# psu_2_1.net
KiCad netlist of a schematic drawn in EAGLE
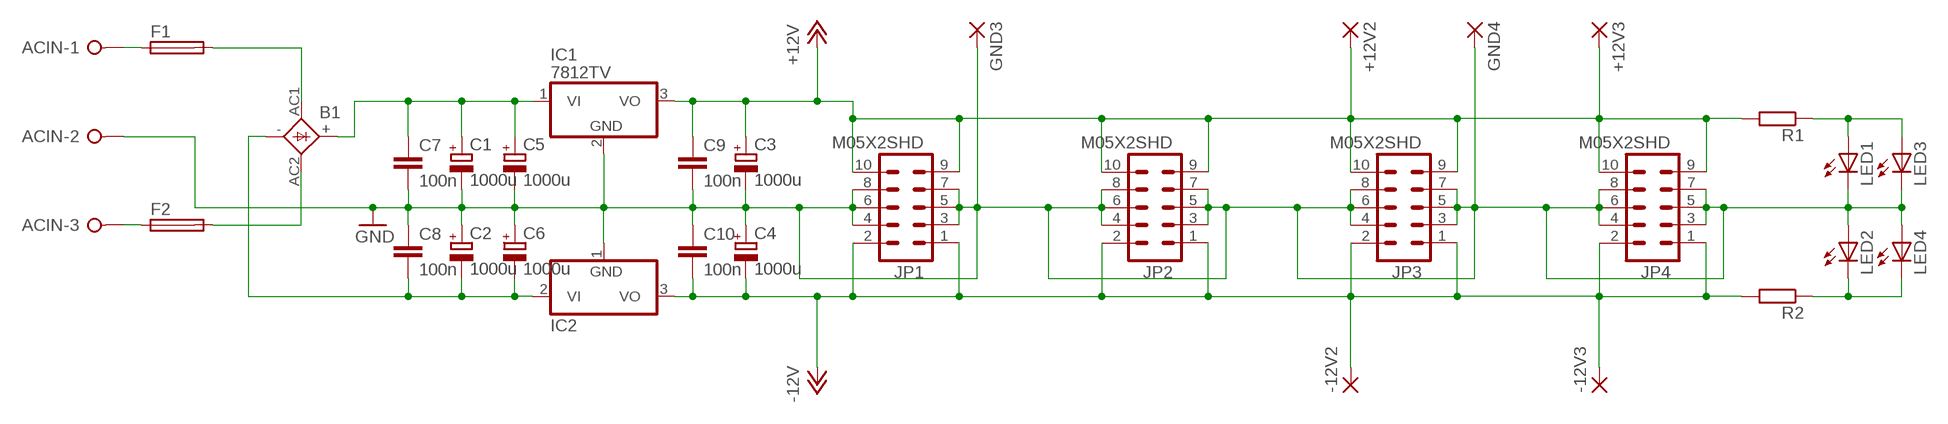
[diagram p0: schematic, sheet 1]

(export (version "E")
  (design (tool "Eeschema 10.0.6"))
  (components
    (comp (ref "+12V2")
      (value "2,54/1,0")
      (footprint "eagle-import:2,54_1,0")
      (libsource (lib "eagle-import") (part "2,54/1,0"))
    )
    (comp (ref "+12V3")
      (value "2,54/1,0")
      (footprint "eagle-import:2,54_1,0")
      (libsource (lib "eagle-import") (part "2,54/1,0"))
    )
    (comp (ref "-12V2")
      (value "2,54/1,0")
      (footprint "eagle-import:2,54_1,0")
      (libsource (lib "eagle-import") (part "2,54/1,0"))
    )
    (comp (ref "-12V3")
      (value "2,54/1,0")
      (footprint "eagle-import:2,54_1,0")
      (libsource (lib "eagle-import") (part "2,54/1,0"))
    )
    (comp (ref "ACIN")
      (value "W237-3E")
      (footprint "eagle-import:W237-3E")
      (libsource (lib "eagle-import") (part "W237-3E"))
    )
    (comp (ref "B1")
      (value "2KBP")
      (footprint "eagle-import:2KBP")
      (libsource (lib "eagle-import") (part "2KBP"))
    )
    (comp (ref "C1")
      (value "1000u")
      (footprint "eagle-import:E3,5-10")
      (libsource (lib "eagle-import") (part "CPOL-EUE3.5-10"))
    )
    (comp (ref "C2")
      (value "1000u")
      (footprint "eagle-import:E3,5-10")
      (libsource (lib "eagle-import") (part "CPOL-EUE3.5-10"))
    )
    (comp (ref "C3")
      (value "1000u")
      (footprint "eagle-import:E3,5-10")
      (libsource (lib "eagle-import") (part "CPOL-EUE3.5-10"))
    )
    (comp (ref "C4")
      (value "1000u")
      (footprint "eagle-import:E3,5-10")
      (libsource (lib "eagle-import") (part "CPOL-EUE3.5-10"))
    )
    (comp (ref "C5")
      (value "1000u")
      (footprint "eagle-import:E3,5-10")
      (libsource (lib "eagle-import") (part "CPOL-EUE3.5-10"))
    )
    (comp (ref "C6")
      (value "1000u")
      (footprint "eagle-import:E3,5-10")
      (libsource (lib "eagle-import") (part "CPOL-EUE3.5-10"))
    )
    (comp (ref "C7")
      (value "100n")
      (footprint "eagle-import:C1206K")
      (libsource (lib "eagle-import") (part "C-EUC1206K"))
    )
    (comp (ref "C8")
      (value "100n")
      (footprint "eagle-import:C1206K")
      (libsource (lib "eagle-import") (part "C-EUC1206K"))
    )
    (comp (ref "C9")
      (value "100n")
      (footprint "eagle-import:C1206K")
      (libsource (lib "eagle-import") (part "C-EUC1206K"))
    )
    (comp (ref "C10")
      (value "100n")
      (footprint "eagle-import:C1206K")
      (libsource (lib "eagle-import") (part "C-EUC1206K"))
    )
    (comp (ref "F1")
      (value "19560")
      (footprint "eagle-import:19560")
      (fields (field (name "MPN") "56000001009"))
      (libsource (lib "eagle-import") (part "19560"))
    )
    (comp (ref "F2")
      (value "19560")
      (footprint "eagle-import:19560")
      (fields (field (name "MPN") "56000001009"))
      (libsource (lib "eagle-import") (part "19560"))
    )
    (comp (ref "GND3")
      (value "2,54/1,0")
      (footprint "eagle-import:2,54_1,0")
      (libsource (lib "eagle-import") (part "2,54/1,0"))
    )
    (comp (ref "GND4")
      (value "2,54/1,0")
      (footprint "eagle-import:2,54_1,0")
      (libsource (lib "eagle-import") (part "2,54/1,0"))
    )
    (comp (ref "IC1")
      (value "7812TV")
      (footprint "eagle-import:TO220V")
      (libsource (lib "eagle-import") (part "78TV12"))
    )
    (comp (ref "IC2")
      (value "7912TV")
      (footprint "eagle-import:TO220V")
      (libsource (lib "eagle-import") (part "79TV12"))
    )
    (comp (ref "JP1")
      (value "M05X2SHD")
      (footprint "eagle-import:2X5-SHROUDED")
      (libsource (lib "eagle-import") (part "M05X2SHD"))
    )
    (comp (ref "JP2")
      (value "M05X2SHD")
      (footprint "eagle-import:2X5-SHROUDED")
      (libsource (lib "eagle-import") (part "M05X2SHD"))
    )
    (comp (ref "JP3")
      (value "M05X2SHD")
      (footprint "eagle-import:2X5-SHROUDED")
      (libsource (lib "eagle-import") (part "M05X2SHD"))
    )
    (comp (ref "JP4")
      (value "M05X2SHD")
      (footprint "eagle-import:2X5-SHROUDED")
      (libsource (lib "eagle-import") (part "M05X2SHD"))
    )
    (comp (ref "LED1")
      (value "LED3MM")
      (footprint "eagle-import:LED3MM")
      (libsource (lib "eagle-import") (part "LED3MM"))
    )
    (comp (ref "LED2")
      (value "LED3MM")
      (footprint "eagle-import:LED3MM")
      (libsource (lib "eagle-import") (part "LED3MM"))
    )
    (comp (ref "LED3")
      (value "LEDCHIPLED_1206")
      (footprint "eagle-import:CHIPLED_1206")
      (libsource (lib "eagle-import") (part "LEDCHIPLED_1206"))
    )
    (comp (ref "LED4")
      (value "LEDCHIPLED_1206")
      (footprint "eagle-import:CHIPLED_1206")
      (libsource (lib "eagle-import") (part "LEDCHIPLED_1206"))
    )
    (comp (ref "R1")
      (value "R-EU_M1206")
      (footprint "eagle-import:M1206")
      (libsource (lib "eagle-import") (part "R-EU_M1206"))
    )
    (comp (ref "R2")
      (value "R-EU_M1206")
      (footprint "eagle-import:M1206")
      (libsource (lib "eagle-import") (part "R-EU_M1206"))
    )
  )
  (nets
    (net (code "1") (name "+12V") (class "Default")
      (node (ref "+12V2") (pin "1") (pinfunction "P_1") (pintype "passive"))
      (node (ref "+12V3") (pin "1") (pinfunction "P_1") (pintype "passive"))
      (node (ref "C3") (pin "+") (pinfunction "+_+") (pintype "passive"))
      (node (ref "C9") (pin "1") (pinfunction "1_1") (pintype "passive"))
      (node (ref "IC1") (pin "3") (pinfunction "VO_3") (pintype "passive"))
      (node (ref "JP1") (pin "10") (pinfunction "10_10") (pintype "passive"))
      (node (ref "JP1") (pin "9") (pinfunction "9_9") (pintype "passive"))
      (node (ref "JP2") (pin "10") (pinfunction "10_10") (pintype "passive"))
      (node (ref "JP2") (pin "9") (pinfunction "9_9") (pintype "passive"))
      (node (ref "JP3") (pin "10") (pinfunction "10_10") (pintype "passive"))
      (node (ref "JP3") (pin "9") (pinfunction "9_9") (pintype "passive"))
      (node (ref "JP4") (pin "10") (pinfunction "10_10") (pintype "passive"))
      (node (ref "JP4") (pin "9") (pinfunction "9_9") (pintype "passive"))
      (node (ref "R1") (pin "2") (pinfunction "2_2") (pintype "passive"))
    )
    (net (code "2") (name "-12V") (class "Default")
      (node (ref "-12V2") (pin "1") (pinfunction "P_1") (pintype "passive"))
      (node (ref "-12V3") (pin "1") (pinfunction "P_1") (pintype "passive"))
      (node (ref "C10") (pin "2") (pinfunction "2_2") (pintype "passive"))
      (node (ref "C4") (pin "-") (pinfunction "-_-") (pintype "passive"))
      (node (ref "IC2") (pin "3") (pinfunction "VO_3") (pintype "passive"))
      (node (ref "JP1") (pin "1") (pinfunction "1_1") (pintype "passive"))
      (node (ref "JP1") (pin "2") (pinfunction "2_2") (pintype "passive"))
      (node (ref "JP2") (pin "1") (pinfunction "1_1") (pintype "passive"))
      (node (ref "JP2") (pin "2") (pinfunction "2_2") (pintype "passive"))
      (node (ref "JP3") (pin "1") (pinfunction "1_1") (pintype "passive"))
      (node (ref "JP3") (pin "2") (pinfunction "2_2") (pintype "passive"))
      (node (ref "JP4") (pin "1") (pinfunction "1_1") (pintype "passive"))
      (node (ref "JP4") (pin "2") (pinfunction "2_2") (pintype "passive"))
      (node (ref "R2") (pin "2") (pinfunction "2_2") (pintype "passive"))
    )
    (net (code "3") (name "GND") (class "Default")
      (node (ref "ACIN") (pin "2") (pinfunction "KL_2") (pintype "passive"))
      (node (ref "C1") (pin "-") (pinfunction "-_-") (pintype "passive"))
      (node (ref "C10") (pin "1") (pinfunction "1_1") (pintype "passive"))
      (node (ref "C2") (pin "+") (pinfunction "+_+") (pintype "passive"))
      (node (ref "C3") (pin "-") (pinfunction "-_-") (pintype "passive"))
      (node (ref "C4") (pin "+") (pinfunction "+_+") (pintype "passive"))
      (node (ref "C5") (pin "-") (pinfunction "-_-") (pintype "passive"))
      (node (ref "C6") (pin "+") (pinfunction "+_+") (pintype "passive"))
      (node (ref "C7") (pin "2") (pinfunction "2_2") (pintype "passive"))
      (node (ref "C8") (pin "1") (pinfunction "1_1") (pintype "passive"))
      (node (ref "C9") (pin "2") (pinfunction "2_2") (pintype "passive"))
      (node (ref "GND3") (pin "1") (pinfunction "P_1") (pintype "passive"))
      (node (ref "GND4") (pin "1") (pinfunction "P_1") (pintype "passive"))
      (node (ref "IC1") (pin "2") (pinfunction "GND_2") (pintype "passive"))
      (node (ref "IC2") (pin "1") (pinfunction "GND_1") (pintype "passive"))
      (node (ref "JP1") (pin "3") (pinfunction "3_3") (pintype "passive"))
      (node (ref "JP1") (pin "4") (pinfunction "4_4") (pintype "passive"))
      (node (ref "JP1") (pin "5") (pinfunction "5_5") (pintype "passive"))
      (node (ref "JP1") (pin "6") (pinfunction "6_6") (pintype "passive"))
      (node (ref "JP1") (pin "7") (pinfunction "7_7") (pintype "passive"))
      (node (ref "JP1") (pin "8") (pinfunction "8_8") (pintype "passive"))
      (node (ref "JP2") (pin "3") (pinfunction "3_3") (pintype "passive"))
      (node (ref "JP2") (pin "4") (pinfunction "4_4") (pintype "passive"))
      (node (ref "JP2") (pin "5") (pinfunction "5_5") (pintype "passive"))
      (node (ref "JP2") (pin "6") (pinfunction "6_6") (pintype "passive"))
      (node (ref "JP2") (pin "7") (pinfunction "7_7") (pintype "passive"))
      (node (ref "JP2") (pin "8") (pinfunction "8_8") (pintype "passive"))
      (node (ref "JP3") (pin "3") (pinfunction "3_3") (pintype "passive"))
      (node (ref "JP3") (pin "4") (pinfunction "4_4") (pintype "passive"))
      (node (ref "JP3") (pin "5") (pinfunction "5_5") (pintype "passive"))
      (node (ref "JP3") (pin "6") (pinfunction "6_6") (pintype "passive"))
      (node (ref "JP3") (pin "7") (pinfunction "7_7") (pintype "passive"))
      (node (ref "JP3") (pin "8") (pinfunction "8_8") (pintype "passive"))
      (node (ref "JP4") (pin "3") (pinfunction "3_3") (pintype "passive"))
      (node (ref "JP4") (pin "4") (pinfunction "4_4") (pintype "passive"))
      (node (ref "JP4") (pin "5") (pinfunction "5_5") (pintype "passive"))
      (node (ref "JP4") (pin "6") (pinfunction "6_6") (pintype "passive"))
      (node (ref "JP4") (pin "7") (pinfunction "7_7") (pintype "passive"))
      (node (ref "JP4") (pin "8") (pinfunction "8_8") (pintype "passive"))
      (node (ref "LED1") (pin "K") (pinfunction "C_K") (pintype "passive"))
      (node (ref "LED2") (pin "A") (pinfunction "A_A") (pintype "passive"))
      (node (ref "LED3") (pin "C") (pinfunction "C_C") (pintype "passive"))
      (node (ref "LED4") (pin "A") (pinfunction "A_A") (pintype "passive"))
    )
    (net (code "4") (name "Net-(ACINA-KL)") (class "Default")
      (node (ref "ACIN") (pin "1") (pinfunction "KL_1") (pintype "passive"))
      (node (ref "F1") (pin "1") (pinfunction "1_1") (pintype "passive"))
    )
    (net (code "5") (name "Net-(ACINC-KL)") (class "Default")
      (node (ref "ACIN") (pin "3") (pinfunction "KL_3") (pintype "passive"))
      (node (ref "F2") (pin "1") (pinfunction "1_1") (pintype "passive"))
    )
    (net (code "6") (name "Net-(B1-PadAC1)") (class "Default")
      (node (ref "B1") (pin "AC1") (pinfunction "AC1_AC1") (pintype "passive"))
      (node (ref "F1") (pin "2") (pinfunction "2_2") (pintype "passive"))
    )
    (net (code "7") (name "Net-(B1-PadAC2)") (class "Default")
      (node (ref "B1") (pin "AC2") (pinfunction "AC2_AC2") (pintype "passive"))
      (node (ref "F2") (pin "2") (pinfunction "2_2") (pintype "passive"))
    )
    (net (code "8") (name "Net-(IC1-VI)") (class "Default")
      (node (ref "B1") (pin "+") (pinfunction "+_+") (pintype "passive"))
      (node (ref "C1") (pin "+") (pinfunction "+_+") (pintype "passive"))
      (node (ref "C5") (pin "+") (pinfunction "+_+") (pintype "passive"))
      (node (ref "C7") (pin "1") (pinfunction "1_1") (pintype "passive"))
      (node (ref "IC1") (pin "1") (pinfunction "VI_1") (pintype "input"))
    )
    (net (code "9") (name "Net-(IC2-VI)") (class "Default")
      (node (ref "B1") (pin "-") (pinfunction "-_-") (pintype "passive"))
      (node (ref "C2") (pin "-") (pinfunction "-_-") (pintype "passive"))
      (node (ref "C6") (pin "-") (pinfunction "-_-") (pintype "passive"))
      (node (ref "C8") (pin "2") (pinfunction "2_2") (pintype "passive"))
      (node (ref "IC2") (pin "2") (pinfunction "VI_2") (pintype "input"))
    )
    (net (code "10") (name "Net-(LED1-PadA)") (class "Default")
      (node (ref "LED1") (pin "A") (pinfunction "A_A") (pintype "passive"))
      (node (ref "LED3") (pin "A") (pinfunction "A_A") (pintype "passive"))
      (node (ref "R1") (pin "1") (pinfunction "1_1") (pintype "passive"))
    )
    (net (code "11") (name "Net-(LED2-C)") (class "Default")
      (node (ref "LED2") (pin "K") (pinfunction "C_K") (pintype "passive"))
      (node (ref "LED4") (pin "C") (pinfunction "C_C") (pintype "passive"))
      (node (ref "R2") (pin "1") (pinfunction "1_1") (pintype "passive"))
    )
  )
)
